# Sheet1.net
KiCad netlist of a schematic drawn in Altium Designer
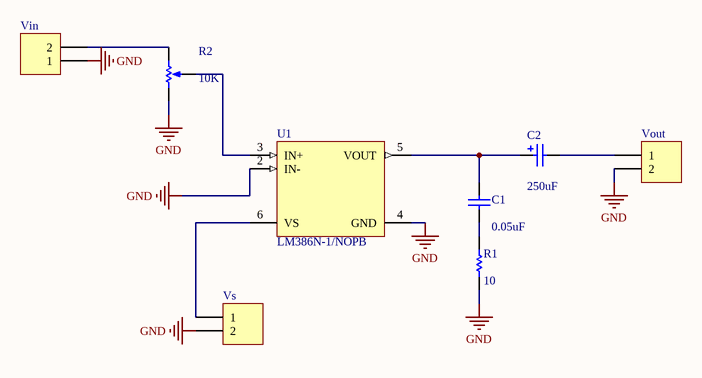
[diagram p0: Sheet1.SchDoc]

(export (version "E")
  (design (tool "Eeschema 10.0.6"))
  (components
    (comp (ref "C1")
      (value "0.05uF")
      (footprint "C1206")
      (description "Capacitor (Semiconductor SIM Model)")
      (fields (field (name "PUBLISHER") "Altium Limited"))
      (libsource (lib "Miscellaneous Devices") (part "Cap Semi"))
    )
    (comp (ref "C2")
      (value "250uF")
      (footprint "Capacitor elec 5MM (3PP)")
      (libsource (lib "CustomLib") (part "Capacitor Electrolytic"))
    )
    (comp (ref "R1")
      (value "10")
      (footprint "AXIAL-0.3")
      (description "Resistor")
      (fields (field (name "PUBLISHER") "Altium Limited"))
      (libsource (lib "Miscellaneous Devices") (part "Res1"))
    )
    (comp (ref "R2")
      (value "10K")
      (footprint "Pot metal slanted")
      (description "Rotary Potentiometer")
      (libsource (lib "CustomLib") (part "Rotary Potentiometer"))
    )
    (comp (ref "U1")
      (value "LM386N-1/NOPB")
      (footprint "N08E")
      (description "Low Voltage Audio Power Amplifier, 8-pin MDIP, Pb-Free")
      (fields
        (field (name "MANUFACTURER") "National Semiconductor")
        (field (name "PUBLISHER") "Altium Limited")
      )
      (libsource (lib "NSC Audio") (part "LM386N-1/NOPB"))
    )
    (comp (ref "Vin")
      (value "~")
      (footprint "HDR1X2")
      (description "Header, 2-Pin")
      (fields (field (name "PUBLISHER") "Altium Limited"))
      (libsource (lib "") (part "Header 2_1"))
    )
    (comp (ref "Vout")
      (value "~")
      (footprint "HDR1X2")
      (description "Header, 2-Pin")
      (fields (field (name "PUBLISHER") "Altium Limited"))
      (libsource (lib "Miscellaneous Connectors") (part "Header 2"))
    )
    (comp (ref "Vs")
      (value "~")
      (footprint "HDR1X2")
      (description "Header, 2-Pin")
      (fields (field (name "PUBLISHER") "Altium Limited"))
      (libsource (lib "Miscellaneous Connectors") (part "Header 2"))
    )
  )
  (nets
    (net (code "1") (name "GND") (class "Default")
      (node (ref "R1") (pin "1") (pinfunction "1_1") (pintype "passive"))
      (node (ref "R2") (pin "1") (pinfunction "TOP_1") (pintype "passive"))
      (node (ref "U1") (pin "2") (pinfunction "IN-_2") (pintype "input"))
      (node (ref "U1") (pin "4") (pinfunction "GND_4") (pintype "power_in"))
      (node (ref "Vin") (pin "1") (pinfunction "1_1") (pintype "passive"))
      (node (ref "Vout") (pin "2") (pinfunction "2_2") (pintype "passive"))
      (node (ref "Vs") (pin "2") (pinfunction "2_2") (pintype "passive"))
    )
    (net (code "2") (name "Net-(C1-Pad1)") (class "Default")
      (node (ref "C1") (pin "1") (pinfunction "1_1") (pintype "passive"))
      (node (ref "R1") (pin "2") (pinfunction "2_2") (pintype "passive"))
    )
    (net (code "3") (name "Net-(C2-Pad2)") (class "Default")
      (node (ref "C2") (pin "2") (pinfunction "2_2") (pintype "passive"))
      (node (ref "Vout") (pin "1") (pinfunction "1_1") (pintype "passive"))
    )
    (net (code "4") (name "Net-(R2-BOT)") (class "Default")
      (node (ref "R2") (pin "3") (pinfunction "BOT_3") (pintype "passive"))
      (node (ref "Vin") (pin "2") (pinfunction "2_2") (pintype "passive"))
    )
    (net (code "5") (name "Net-(R2-TAP)") (class "Default")
      (node (ref "R2") (pin "2") (pinfunction "TAP_2") (pintype "passive"))
      (node (ref "U1") (pin "3") (pinfunction "IN+_3") (pintype "input"))
    )
    (net (code "6") (name "Net-(U1-VOUT)") (class "Default")
      (node (ref "C1") (pin "2") (pinfunction "2_2") (pintype "passive"))
      (node (ref "C2") (pin "1") (pinfunction "1_1") (pintype "passive"))
      (node (ref "U1") (pin "5") (pinfunction "VOUT_5") (pintype "output"))
    )
    (net (code "7") (name "Net-(U1-VS)") (class "Default")
      (node (ref "U1") (pin "6") (pinfunction "VS_6") (pintype "power_in"))
      (node (ref "Vs") (pin "1") (pinfunction "1_1") (pintype "passive"))
    )
  )
)
